# PMW3360-breakout_02_v18.net
KiCad netlist of a schematic drawn in EAGLE
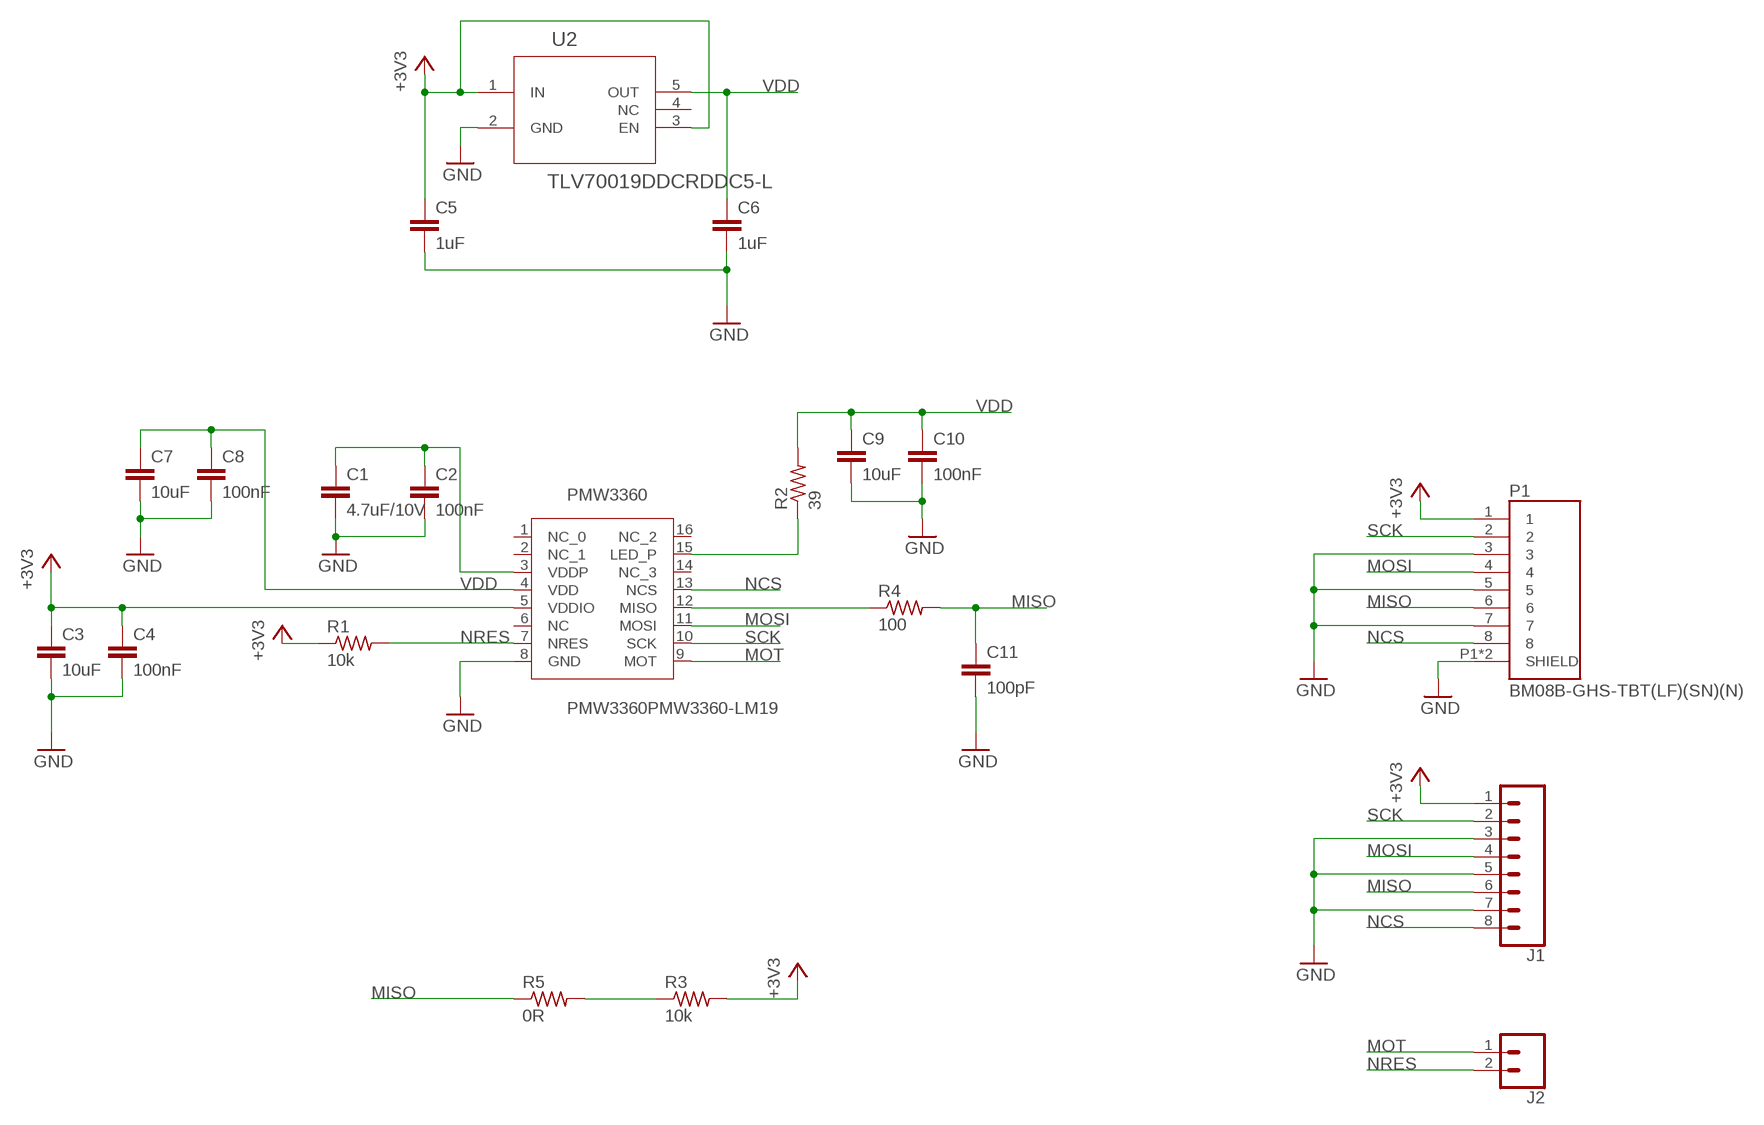
[diagram p0: schematic, sheet 1]

(export (version "E")
  (design (tool "Eeschema 10.0.6"))
  (components
    (comp (ref "C1")
      (value "4.7uF/10V")
      (footprint "eagle-import:CAPC1608X85")
      (libsource (lib "eagle-import") (part "CCHIP-0603(1608-METRIC)_"))
    )
    (comp (ref "C2")
      (value "100nF")
      (footprint "eagle-import:CAPC1005X60")
      (libsource (lib "eagle-import") (part "CCHIP-0402(1005-METRIC)_"))
    )
    (comp (ref "C3")
      (value "10uF")
      (footprint "eagle-import:CAPC1005X60")
      (libsource (lib "eagle-import") (part "CCHIP-0402(1005-METRIC)_"))
    )
    (comp (ref "C4")
      (value "100nF")
      (footprint "eagle-import:CAPC1005X60")
      (libsource (lib "eagle-import") (part "CCHIP-0402(1005-METRIC)_"))
    )
    (comp (ref "C5")
      (value "1uF")
      (footprint "eagle-import:CAPC1005X60")
      (libsource (lib "eagle-import") (part "CCHIP-0402(1005-METRIC)_"))
    )
    (comp (ref "C6")
      (value "1uF")
      (footprint "eagle-import:CAPC1005X60")
      (libsource (lib "eagle-import") (part "CCHIP-0402(1005-METRIC)_"))
    )
    (comp (ref "C7")
      (value "10uF")
      (footprint "eagle-import:CAPC1005X60")
      (libsource (lib "eagle-import") (part "CCHIP-0402(1005-METRIC)_"))
    )
    (comp (ref "C8")
      (value "100nF")
      (footprint "eagle-import:CAPC1005X60")
      (libsource (lib "eagle-import") (part "CCHIP-0402(1005-METRIC)_"))
    )
    (comp (ref "C9")
      (value "10uF")
      (footprint "eagle-import:CAPC1005X60")
      (libsource (lib "eagle-import") (part "CCHIP-0402(1005-METRIC)_"))
    )
    (comp (ref "C10")
      (value "100nF")
      (footprint "eagle-import:CAPC1005X60")
      (libsource (lib "eagle-import") (part "CCHIP-0402(1005-METRIC)_"))
    )
    (comp (ref "C11")
      (value "100pF")
      (footprint "eagle-import:C0402K")
      (libsource (lib "eagle-import") (part "C-EUC0402K"))
    )
    (comp (ref "J1")
      (value "CONN_08\"")
      (footprint "eagle-import:1X08")
      (libsource (lib "eagle-import") (part "CONN_08{dblquote}"))
    )
    (comp (ref "J2")
      (value "CONN_02")
      (footprint "eagle-import:1X02")
      (libsource (lib "eagle-import") (part "CONN_02"))
    )
    (comp (ref "P1")
      (value "BM08B-GHS-TBT(LF)(SN)(N)")
      (footprint "eagle-import:JST_BM08B-GHS-TBT(LF)(SN)(N)")
      (fields (field (name "MF") "JST Sales"))
      (libsource (lib "eagle-import") (part "BM08B-GHS-TBT(LF)(SN)(N)"))
    )
    (comp (ref "PMW3360")
      (value "PMW3360PMW3360-LM19")
      (footprint "eagle-import:PMW3360")
      (libsource (lib "eagle-import") (part "PMW3360PMW3360-LM19"))
    )
    (comp (ref "R1")
      (value "10k")
      (footprint "eagle-import:R0402")
      (libsource (lib "eagle-import") (part "R-US_R0402"))
    )
    (comp (ref "R2")
      (value "39")
      (footprint "eagle-import:R0402")
      (libsource (lib "eagle-import") (part "R-US_R0402"))
    )
    (comp (ref "R3")
      (value "10k")
      (footprint "eagle-import:R0402")
      (libsource (lib "eagle-import") (part "R-US_R0402"))
    )
    (comp (ref "R4")
      (value "100")
      (footprint "eagle-import:R0402")
      (libsource (lib "eagle-import") (part "R-US_R0402"))
    )
    (comp (ref "R5")
      (value "0R")
      (footprint "eagle-import:R0402")
      (libsource (lib "eagle-import") (part "R-US_R0402"))
    )
    (comp (ref "U2")
      (value "TLV70019DDCRDDC5-L")
      (footprint "eagle-import:DDC5-L")
      (fields
        (field (name "MANUFACTURER_PART_NUMBER") "TLV70019DDCR")
        (field (name "COPYRIGHT") "Copyright (C) 2024 Ultra Librarian. All rights reserved.")
      )
      (libsource (lib "eagle-import") (part "TLV70019DDCRDDC5-L"))
    )
  )
  (nets
    (net (code "1") (name "+3V3") (class "Default")
      (node (ref "C3") (pin "1") (pinfunction "1_1") (pintype "passive"))
      (node (ref "C4") (pin "1") (pinfunction "1_1") (pintype "passive"))
      (node (ref "C5") (pin "1") (pinfunction "1_1") (pintype "passive"))
      (node (ref "J1") (pin "1") (pinfunction "1_1") (pintype "passive"))
      (node (ref "P1") (pin "1") (pinfunction "1_1") (pintype "passive"))
      (node (ref "PMW3360") (pin "5") (pinfunction "VDDIO_5") (pintype "power_in"))
      (node (ref "R1") (pin "1") (pinfunction "1_1") (pintype "passive"))
      (node (ref "R3") (pin "2") (pinfunction "2_2") (pintype "passive"))
      (node (ref "U2") (pin "1") (pinfunction "IN_1") (pintype "input"))
      (node (ref "U2") (pin "3") (pinfunction "EN_3") (pintype "passive"))
    )
    (net (code "2") (name "/MISO") (class "Default")
      (node (ref "C11") (pin "1") (pinfunction "1_1") (pintype "passive"))
      (node (ref "J1") (pin "6") (pinfunction "6_6") (pintype "passive"))
      (node (ref "P1") (pin "6") (pinfunction "6_6") (pintype "passive"))
      (node (ref "R4") (pin "2") (pinfunction "2_2") (pintype "passive"))
      (node (ref "R5") (pin "1") (pinfunction "1_1") (pintype "passive"))
    )
    (net (code "3") (name "/MOSI") (class "Default")
      (node (ref "J1") (pin "4") (pinfunction "4_4") (pintype "passive"))
      (node (ref "P1") (pin "4") (pinfunction "4_4") (pintype "passive"))
      (node (ref "PMW3360") (pin "11") (pinfunction "MOSI_11") (pintype "input"))
    )
    (net (code "4") (name "/MOT") (class "Default")
      (node (ref "J2") (pin "1") (pinfunction "1_1") (pintype "passive"))
      (node (ref "PMW3360") (pin "9") (pinfunction "MOT_9") (pintype "output"))
    )
    (net (code "5") (name "/NCS") (class "Default")
      (node (ref "J1") (pin "8") (pinfunction "8_8") (pintype "passive"))
      (node (ref "P1") (pin "8") (pinfunction "8_8") (pintype "passive"))
      (node (ref "PMW3360") (pin "13") (pinfunction "NCS_13") (pintype "input"))
    )
    (net (code "6") (name "/NRES") (class "Default")
      (node (ref "J2") (pin "2") (pinfunction "2_2") (pintype "passive"))
      (node (ref "PMW3360") (pin "7") (pinfunction "NRES_7") (pintype "input"))
      (node (ref "R1") (pin "2") (pinfunction "2_2") (pintype "passive"))
    )
    (net (code "7") (name "/SCK") (class "Default")
      (node (ref "J1") (pin "2") (pinfunction "2_2") (pintype "passive"))
      (node (ref "P1") (pin "2") (pinfunction "2_2") (pintype "passive"))
      (node (ref "PMW3360") (pin "10") (pinfunction "SCK_10") (pintype "input"))
    )
    (net (code "8") (name "/VDD") (class "Default")
      (node (ref "C10") (pin "1") (pinfunction "1_1") (pintype "passive"))
      (node (ref "C6") (pin "1") (pinfunction "1_1") (pintype "passive"))
      (node (ref "C7") (pin "1") (pinfunction "1_1") (pintype "passive"))
      (node (ref "C8") (pin "1") (pinfunction "1_1") (pintype "passive"))
      (node (ref "C9") (pin "1") (pinfunction "1_1") (pintype "passive"))
      (node (ref "PMW3360") (pin "4") (pinfunction "VDD_4") (pintype "power_in"))
      (node (ref "R2") (pin "2") (pinfunction "2_2") (pintype "passive"))
      (node (ref "U2") (pin "5") (pinfunction "OUT_5") (pintype "output"))
    )
    (net (code "9") (name "GND") (class "Default")
      (node (ref "C1") (pin "2") (pinfunction "2_2") (pintype "passive"))
      (node (ref "C10") (pin "2") (pinfunction "2_2") (pintype "passive"))
      (node (ref "C11") (pin "2") (pinfunction "2_2") (pintype "passive"))
      (node (ref "C2") (pin "2") (pinfunction "2_2") (pintype "passive"))
      (node (ref "C3") (pin "2") (pinfunction "2_2") (pintype "passive"))
      (node (ref "C4") (pin "2") (pinfunction "2_2") (pintype "passive"))
      (node (ref "C5") (pin "2") (pinfunction "2_2") (pintype "passive"))
      (node (ref "C6") (pin "2") (pinfunction "2_2") (pintype "passive"))
      (node (ref "C7") (pin "2") (pinfunction "2_2") (pintype "passive"))
      (node (ref "C8") (pin "2") (pinfunction "2_2") (pintype "passive"))
      (node (ref "C9") (pin "2") (pinfunction "2_2") (pintype "passive"))
      (node (ref "J1") (pin "3") (pinfunction "3_3") (pintype "passive"))
      (node (ref "J1") (pin "5") (pinfunction "5_5") (pintype "passive"))
      (node (ref "J1") (pin "7") (pinfunction "7_7") (pintype "passive"))
      (node (ref "P1") (pin "3") (pinfunction "3_3") (pintype "passive"))
      (node (ref "P1") (pin "5") (pinfunction "5_5") (pintype "passive"))
      (node (ref "P1") (pin "7") (pinfunction "7_7") (pintype "passive"))
      (node (ref "P1") (pin "P1") (pinfunction "SHIELD_P1") (pintype "passive"))
      (node (ref "P1") (pin "P2") (pinfunction "SHIELD_P2") (pintype "passive"))
      (node (ref "PMW3360") (pin "8") (pinfunction "GND_8") (pintype "power_in"))
      (node (ref "U2") (pin "2") (pinfunction "GND_2") (pintype "power_in"))
    )
    (net (code "10") (name "Net-(PMW3360-LED_P)") (class "Default")
      (node (ref "PMW3360") (pin "15") (pinfunction "LED_P_15") (pintype "input"))
      (node (ref "R2") (pin "1") (pinfunction "1_1") (pintype "passive"))
    )
    (net (code "11") (name "Net-(PMW3360-MISO)") (class "Default")
      (node (ref "PMW3360") (pin "12") (pinfunction "MISO_12") (pintype "output"))
      (node (ref "R4") (pin "1") (pinfunction "1_1") (pintype "passive"))
    )
    (net (code "12") (name "Net-(PMW3360-VDDP)") (class "Default")
      (node (ref "C1") (pin "1") (pinfunction "1_1") (pintype "passive"))
      (node (ref "C2") (pin "1") (pinfunction "1_1") (pintype "passive"))
      (node (ref "PMW3360") (pin "3") (pinfunction "VDDP_3") (pintype "power_in"))
    )
    (net (code "13") (name "Net-(R3-Pad1)") (class "Default")
      (node (ref "R3") (pin "1") (pinfunction "1_1") (pintype "passive"))
      (node (ref "R5") (pin "2") (pinfunction "2_2") (pintype "passive"))
    )
    (net (code "14") (name "unconnected-(PMW3360-NC-Pad6)") (class "Default")
      (node (ref "PMW3360") (pin "6") (pinfunction "NC_6") (pintype "no_connect"))
    )
    (net (code "15") (name "unconnected-(PMW3360-NC_0-Pad1)") (class "Default")
      (node (ref "PMW3360") (pin "1") (pinfunction "NC_0_1") (pintype "no_connect"))
    )
    (net (code "16") (name "unconnected-(PMW3360-NC_1-Pad2)") (class "Default")
      (node (ref "PMW3360") (pin "2") (pinfunction "NC_1_2") (pintype "no_connect"))
    )
    (net (code "17") (name "unconnected-(PMW3360-NC_2-Pad16)") (class "Default")
      (node (ref "PMW3360") (pin "16") (pinfunction "NC_2_16") (pintype "no_connect"))
    )
    (net (code "18") (name "unconnected-(PMW3360-NC_3-Pad14)") (class "Default")
      (node (ref "PMW3360") (pin "14") (pinfunction "NC_3_14") (pintype "no_connect"))
    )
    (net (code "19") (name "unconnected-(U2-NC-Pad4)") (class "Default")
      (node (ref "U2") (pin "4") (pinfunction "NC_4") (pintype "passive"))
    )
  )
)
